# ButtonCircuit.net
KiCad netlist of a schematic drawn in Altium Designer
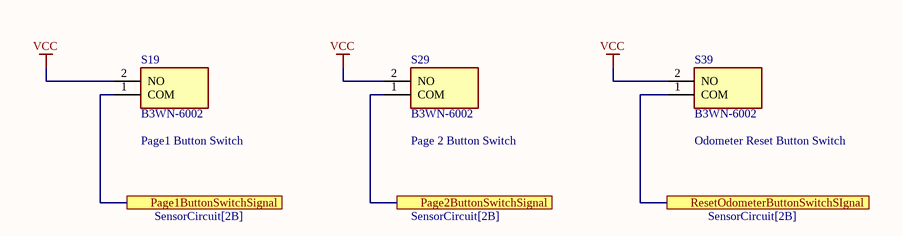
[diagram p0: ButtonCircuit.SchDoc]

(export (version "E")
  (design (tool "Eeschema 10.0.6"))
  (components
    (comp (ref "S19")
      (value "B3WN-6002")
      (footprint "SamacSys:B3WN6002")
      (description "Switch")
      (fields (field (name "MOUSER PART NUMBER") "653-B3WN-6002"))
      (libsource (lib "SamacSys") (part "B3WN-6002"))
    )
    (comp (ref "S29")
      (value "B3WN-6002")
      (footprint "SamacSys:B3WN6002")
      (description "Switch")
      (fields (field (name "MOUSER PART NUMBER") "653-B3WN-6002"))
      (libsource (lib "SamacSys") (part "B3WN-6002"))
    )
    (comp (ref "S39")
      (value "B3WN-6002")
      (footprint "SamacSys:B3WN6002")
      (description "Switch")
      (fields (field (name "MOUSER PART NUMBER") "653-B3WN-6002"))
      (libsource (lib "SamacSys") (part "B3WN-6002"))
    )
  )
  (nets
    (net (code "1") (name "/Page1ButtonSwitchSignal") (class "Default")
      (node (ref "S19") (pin "1") (pinfunction "COM_1") (pintype "passive"))
    )
    (net (code "2") (name "/Page2ButtonSwitchSignal") (class "Default")
      (node (ref "S29") (pin "1") (pinfunction "COM_1") (pintype "passive"))
    )
    (net (code "3") (name "/ResetOdometerButtonSwitchSIgnal") (class "Default")
      (node (ref "S39") (pin "1") (pinfunction "COM_1") (pintype "passive"))
    )
    (net (code "4") (name "VCC") (class "Default")
      (node (ref "S19") (pin "2") (pinfunction "NO_2") (pintype "passive"))
      (node (ref "S29") (pin "2") (pinfunction "NO_2") (pintype "passive"))
      (node (ref "S39") (pin "2") (pinfunction "NO_2") (pintype "passive"))
    )
  )
)
